# Sheet3.net
KiCad netlist of a schematic drawn in Altium Designer
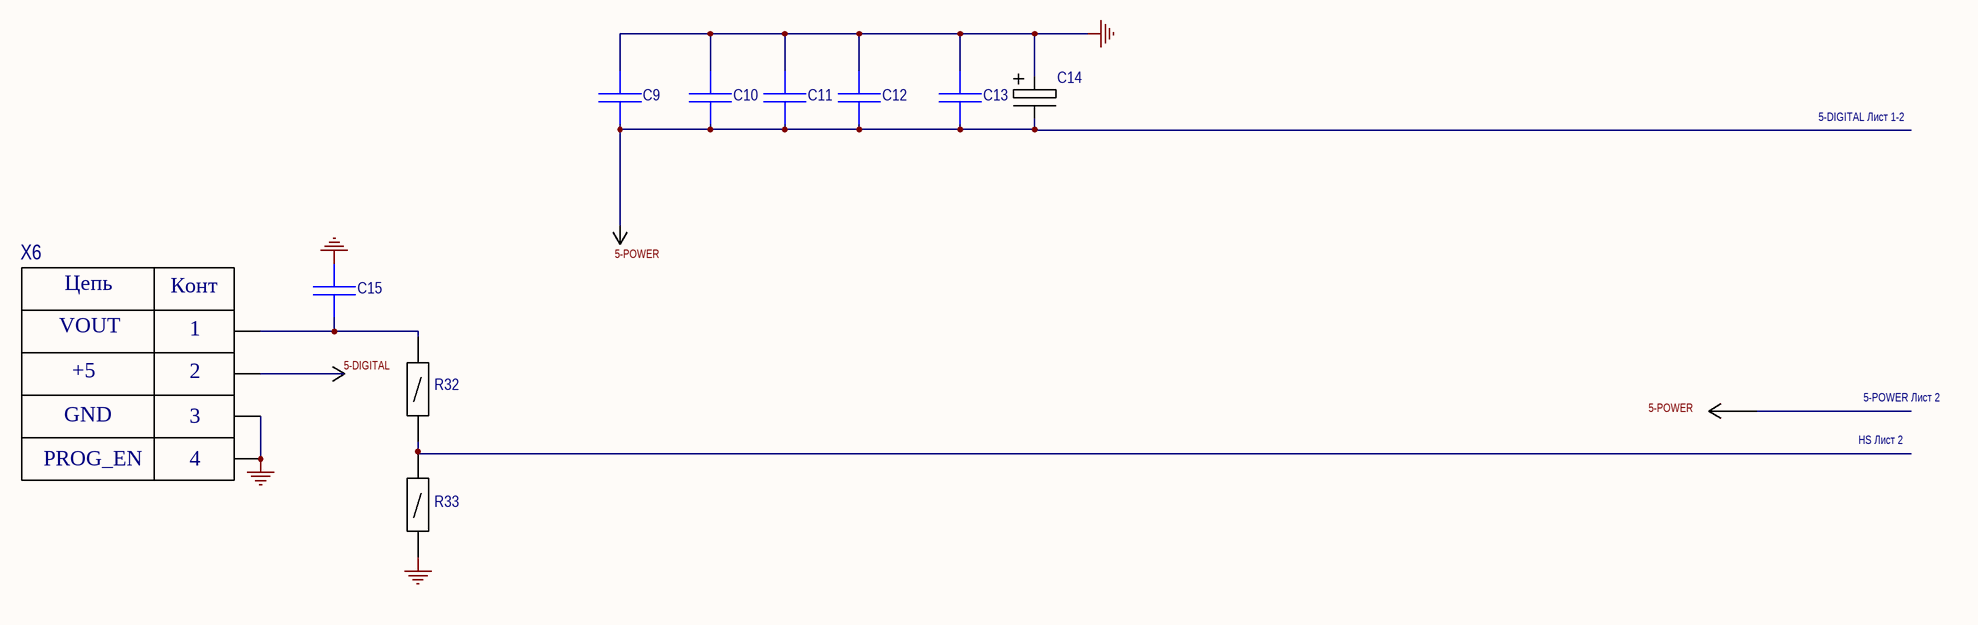
[diagram p0: Sheet3.SchDoc]

(export (version "E")
  (design (tool "Eeschema 10.0.6"))
  (components
    (comp (ref "C9") (value "CAP") (footprint "CAP SMD 1812") (libsource (lib "Schlib1") (part "CAP")))
    (comp (ref "C10") (value "CAP") (footprint "CAP SMD 1206") (libsource (lib "Schlib1") (part "CAP")))
    (comp (ref "C11") (value "CAP") (footprint "CAP SMD 1206") (libsource (lib "Schlib1") (part "CAP")))
    (comp (ref "C12") (value "CAP") (footprint "CAP SMD 1206") (libsource (lib "Schlib1") (part "CAP")))
    (comp (ref "C13") (value "CAP") (footprint "CAP SMD 1206") (libsource (lib "Schlib1") (part "CAP")))
    (comp (ref "C14") (value "~") (footprint "Radial 5x11mm") (libsource (lib "Schlib1") (part "CapPol_1")))
    (comp (ref "C15") (value "CAP") (footprint "CAP SMD 1206") (libsource (lib "Schlib1") (part "CAP")))
    (comp (ref "R32")
      (value "resistor")
      (footprint "RESISTOR SMD 0805")
      (libsource (lib "Schlib1") (part "resistor"))
    )
    (comp (ref "R33")
      (value "resistor")
      (footprint "RESISTOR SMD 0805")
      (libsource (lib "Schlib1") (part "resistor"))
    )
    (comp (ref "X6") (value "PLS3_1") (footprint "PLS4") (libsource (lib "Schlib1") (part "PLS3_1")))
  )
  (nets
    (net (code "1") (name "/5-DIGITAL") (class "Default")
      (node (ref "X6") (pin "2") (pinfunction "2_2") (pintype "passive"))
    )
    (net (code "3") (name "GND") (class "Default")
      (node (ref "C10") (pin "2") (pinfunction "2_2") (pintype "passive"))
      (node (ref "C11") (pin "2") (pinfunction "2_2") (pintype "passive"))
      (node (ref "C12") (pin "2") (pinfunction "2_2") (pintype "passive"))
      (node (ref "C13") (pin "2") (pinfunction "2_2") (pintype "passive"))
      (node (ref "C14") (pin "2") (pinfunction "2_2") (pintype "passive"))
      (node (ref "C15") (pin "2") (pinfunction "2_2") (pintype "passive"))
      (node (ref "C9") (pin "2") (pinfunction "2_2") (pintype "passive"))
      (node (ref "R33") (pin "1") (pinfunction "1_1") (pintype "passive"))
      (node (ref "X6") (pin "3") (pinfunction "3_3") (pintype "passive"))
      (node (ref "X6") (pin "4") (pinfunction "4_4") (pintype "passive"))
    )
    (net (code "4") (name "Net-(C10-Pad1)") (class "Default")
      (node (ref "C10") (pin "1") (pinfunction "1_1") (pintype "passive"))
      (node (ref "C11") (pin "1") (pinfunction "1_1") (pintype "passive"))
      (node (ref "C12") (pin "1") (pinfunction "1_1") (pintype "passive"))
      (node (ref "C13") (pin "1") (pinfunction "1_1") (pintype "passive"))
      (node (ref "C14") (pin "1") (pinfunction "1_1") (pintype "passive"))
      (node (ref "C9") (pin "1") (pinfunction "1_1") (pintype "passive"))
    )
    (net (code "5") (name "Net-(C15-Pad1)") (class "Default")
      (node (ref "C15") (pin "1") (pinfunction "1_1") (pintype "passive"))
      (node (ref "R32") (pin "2") (pinfunction "2_2") (pintype "passive"))
      (node (ref "X6") (pin "1") (pinfunction "1_1") (pintype "passive"))
    )
    (net (code "6") (name "Net-(R32-Pad1)") (class "Default")
      (node (ref "R32") (pin "1") (pinfunction "1_1") (pintype "passive"))
      (node (ref "R33") (pin "2") (pinfunction "2_2") (pintype "passive"))
    )
  )
)
